# HandshakeIRemitter.net
KiCad netlist of a schematic drawn in Altium Designer
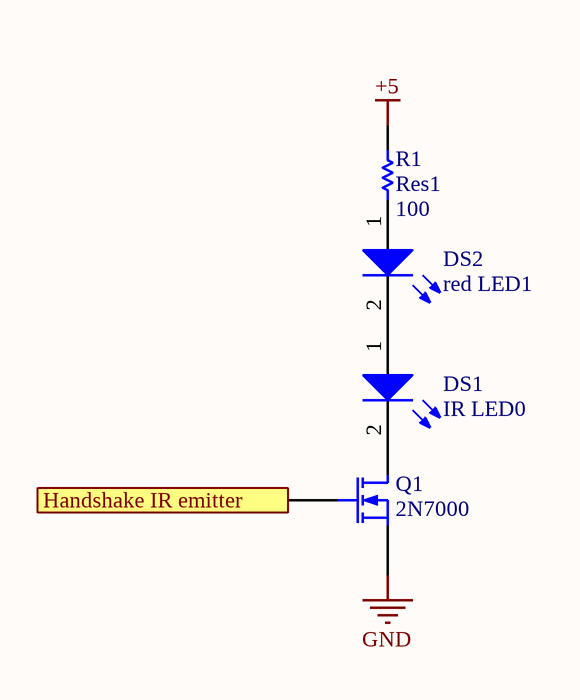
[diagram p0: HandshakeIRemitter.SchDoc]

(export (version "E")
  (design (tool "Eeschema 10.0.6"))
  (components
    (comp (ref "DS1")
      (value "IR LED0")
      (footprint "LED-0")
      (description "Typical INFRARED GaAs LED")
      (fields
        (field (name "MANUFACTURER") "Generic Components")
        (field (name "PUBLISHER") "Altium Hobart Technology Centre")
      )
      (libsource (lib "ME218_BaseLib") (part "LED0"))
    )
    (comp (ref "DS2")
      (value "red LED1")
      (footprint "LED-1")
      (description "Typical RED GaAs LED")
      (fields
        (field (name "MANUFACTURER") "Generic Components")
        (field (name "PUBLISHER") "Altium Hobart Technology Centre")
      )
      (libsource (lib "ME218_BaseLib") (part "LED1"))
    )
    (comp (ref "Q1")
      (value "2N7000")
      (footprint "BCY-W3/D5")
      (description "N-Channel Enhancement Mode Vertical DMOS FET")
      (fields
        (field (name "MANUFACTURER") "Zetex")
        (field (name "PUBLISHER") "Altium Hobart Technology Centre")
      )
      (libsource (lib "ME218_BaseLib") (part "2N7000"))
    )
    (comp (ref "R1")
      (value "Res1")
      (footprint "AXIAL-0.3")
      (description "Resistor")
      (fields
        (field (name "MANUFACTURER") "Generic Components")
        (field (name "ALTIUM_VALUE") "100")
        (field (name "PUBLISHER") "Altium Hobart Technology Centre")
      )
      (libsource (lib "ME218_BaseLib") (part "Res1"))
    )
  )
  (nets
    (net (code "1") (name "+5") (class "Default")
      (node (ref "R1") (pin "1") (pinfunction "1_1") (pintype "passive"))
    )
    (net (code "2") (name "/Handshake IR emitter") (class "Default")
      (node (ref "Q1") (pin "2") (pinfunction "G_2") (pintype "passive"))
    )
    (net (code "3") (name "GND") (class "Default")
      (node (ref "Q1") (pin "1") (pinfunction "S_1") (pintype "passive"))
    )
    (net (code "4") (name "Net-(DS1-A)") (class "Default")
      (node (ref "DS1") (pin "1") (pinfunction "A_1") (pintype "passive"))
      (node (ref "DS2") (pin "2") (pinfunction "K_2") (pintype "passive"))
    )
    (net (code "5") (name "unconnected-(DS1-K-Pad2)") (class "Default")
      (node (ref "DS1") (pin "2") (pinfunction "K_2") (pintype "passive"))
    )
    (net (code "6") (name "unconnected-(DS2-A-Pad1)") (class "Default")
      (node (ref "DS2") (pin "1") (pinfunction "A_1") (pintype "passive"))
    )
    (net (code "7") (name "unconnected-(Q1-D-Pad3)") (class "Default")
      (node (ref "Q1") (pin "3") (pinfunction "D_3") (pintype "passive"))
    )
    (net (code "8") (name "unconnected-(R1-Pad2)") (class "Default")
      (node (ref "R1") (pin "2") (pinfunction "2_2") (pintype "passive"))
    )
  )
)
